# Gate_Driver.net
KiCad netlist of a schematic drawn in Altium Designer
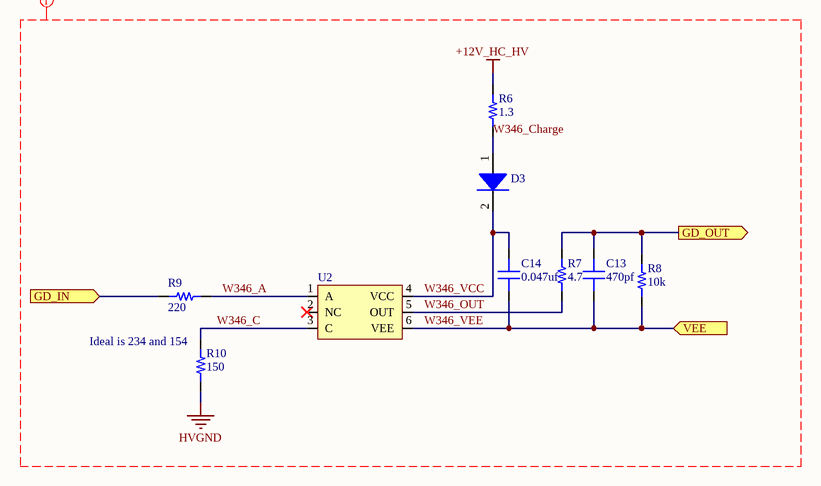
[diagram p0: Gate Driver.SchDoc]

(export (version "E")
  (design (tool "Eeschema 10.0.6"))
  (components
    (comp (ref "C13")
      (value "470pf")
      (footprint "CAP 0603/1608")
      (fields
        (field (name "Comment") "Capacitor MLCC 470pf 50V CAP 0603/1608")
        (field (name "CREATED_BY") "Nick Mah")
      )
      (libsource (lib "Altium-Lib") (part "Capacitor"))
    )
    (comp (ref "C14")
      (value "0.047uf")
      (footprint "CAP 1210/3225 - 1.6MM")
      (fields
        (field (name "Comment") "Capacitor MLCC 50.047uf 630V CAP 1210/3225")
        (field (name "CREATED_BY") "Nick Mah")
      )
      (libsource (lib "Altium-Lib") (part "Capacitor"))
    )
    (comp (ref "D3")
      (value "~")
      (footprint "SMA")
      (description "Diode Standard 1000V 1A Surface Mount SMA")
      (fields
        (field (name "MFRPARTNO") "RS1MTR")
        (field (name "POWER") "1000Vr")
        (field (name "CREATED_BY") "Nick")
      )
      (libsource (lib "Altium-Lib") (part "DIODE"))
    )
    (comp (ref "R6")
      (value "1.3")
      (footprint "RES 1206/3216")
      (description "1.3 Ohms ±1% 0.25W, 1/4W Chip Resistor 1206 (3216 Metric)  Thick Film")
      (fields
        (field (name "TOLERANCE") "1%")
        (field (name "POWER") "1/4W")
        (field (name "CREATED_BY") "Nick Mah")
      )
      (libsource (lib "Altium-Lib") (part "Resistor"))
    )
    (comp (ref "R7")
      (value "4.7")
      (footprint "RES 0805/2012")
      (fields
        (field (name "TOLERANCE") "1%")
        (field (name "POWER") "1/4W")
        (field (name "Comment") "Resistor 4.7 0805 1/4W 1%")
        (field (name "CREATED_BY") "Nick Mah")
      )
      (libsource (lib "Altium-Lib") (part "Resistor"))
    )
    (comp (ref "R8")
      (value "10k")
      (footprint "RES 0603/1608")
      (fields
        (field (name "TOLERANCE") "1%")
        (field (name "POWER") "1/10W")
        (field (name "Comment") "Resistor 10k 0603 1/10W 1%")
        (field (name "CREATED_BY") "Nick Mah")
      )
      (libsource (lib "Altium-Lib") (part "Resistor"))
    )
    (comp (ref "R9")
      (value "220")
      (footprint "RES 0603/1608")
      (fields
        (field (name "TOLERANCE") "5%")
        (field (name "POWER") "1/10W")
        (field (name "Comment") "Resistor 220 0603 1/10W 5%")
        (field (name "CREATED_BY") "Nick Mah")
      )
      (libsource (lib "Altium-Lib") (part "Resistor"))
    )
    (comp (ref "R10")
      (value "150")
      (footprint "RES 0603/1608")
      (fields
        (field (name "TOLERANCE") "5%")
        (field (name "POWER") "1/10W")
        (field (name "Comment") "Resistor 150 0603 1/10W 5%")
        (field (name "CREATED_BY") "Nick Mah")
      )
      (libsource (lib "Altium-Lib") (part "Resistor"))
    )
    (comp (ref "U2")
      (value "~")
      (footprint "SOIC-6 (8-mm Clearance)")
      (description "OPTOISO 5KV 1CH GATE DRIVER 6SO")
      (fields
        (field (name "MFRPARTNO") "ACPL-W346")
        (field (name "POWER") "2.5A")
        (field (name "CREATED_BY") "Nick")
      )
      (libsource (lib "Altium-Lib") (part "ACPL-W346"))
    )
  )
  (nets
    (net (code "1") (name "+12V_HC_HV") (class "Default")
      (node (ref "R6") (pin "2") (pinfunction "2_2") (pintype "passive"))
    )
    (net (code "2") (name "/GD_IN") (class "Default")
      (node (ref "R9") (pin "1") (pinfunction "1_1") (pintype "passive"))
    )
    (net (code "3") (name "/GD_OUT") (class "Default")
      (node (ref "C13") (pin "2") (pinfunction "2_2") (pintype "passive"))
      (node (ref "R7") (pin "2") (pinfunction "2_2") (pintype "passive"))
      (node (ref "R8") (pin "2") (pinfunction "2_2") (pintype "passive"))
    )
    (net (code "4") (name "/W346_A") (class "Default")
      (node (ref "R9") (pin "2") (pinfunction "2_2") (pintype "passive"))
      (node (ref "U2") (pin "1") (pinfunction "A_1") (pintype "passive"))
    )
    (net (code "5") (name "/W346_C") (class "Default")
      (node (ref "R10") (pin "2") (pinfunction "2_2") (pintype "passive"))
      (node (ref "U2") (pin "3") (pinfunction "C_3") (pintype "passive"))
    )
    (net (code "6") (name "/W346_Charge") (class "Default")
      (node (ref "D3") (pin "1") (pinfunction "A_1") (pintype "passive"))
      (node (ref "R6") (pin "1") (pinfunction "1_1") (pintype "passive"))
    )
    (net (code "7") (name "/W346_OUT") (class "Default")
      (node (ref "R7") (pin "1") (pinfunction "1_1") (pintype "passive"))
      (node (ref "U2") (pin "5") (pinfunction "OUT_5") (pintype "output"))
    )
    (net (code "8") (name "/W346_VCC") (class "Default")
      (node (ref "C14") (pin "2") (pinfunction "2_2") (pintype "passive"))
      (node (ref "D3") (pin "2") (pinfunction "K_2") (pintype "passive"))
      (node (ref "U2") (pin "4") (pinfunction "VCC_4") (pintype "passive"))
    )
    (net (code "9") (name "/W346_VEE") (class "Default")
      (node (ref "C13") (pin "1") (pinfunction "1_1") (pintype "passive"))
      (node (ref "C14") (pin "1") (pinfunction "1_1") (pintype "passive"))
      (node (ref "R8") (pin "1") (pinfunction "1_1") (pintype "passive"))
      (node (ref "U2") (pin "6") (pinfunction "VEE_6") (pintype "passive"))
    )
    (net (code "10") (name "HVGND") (class "Default")
      (node (ref "R10") (pin "1") (pinfunction "1_1") (pintype "passive"))
    )
    (net (code "11") (name "unconnected-(U2-NC-Pad2)") (class "Default")
      (node (ref "U2") (pin "2") (pinfunction "NC_2") (pintype "passive+no_connect"))
    )
  )
)
